# ao.net
KiCad netlist of a schematic drawn in Altium Designer
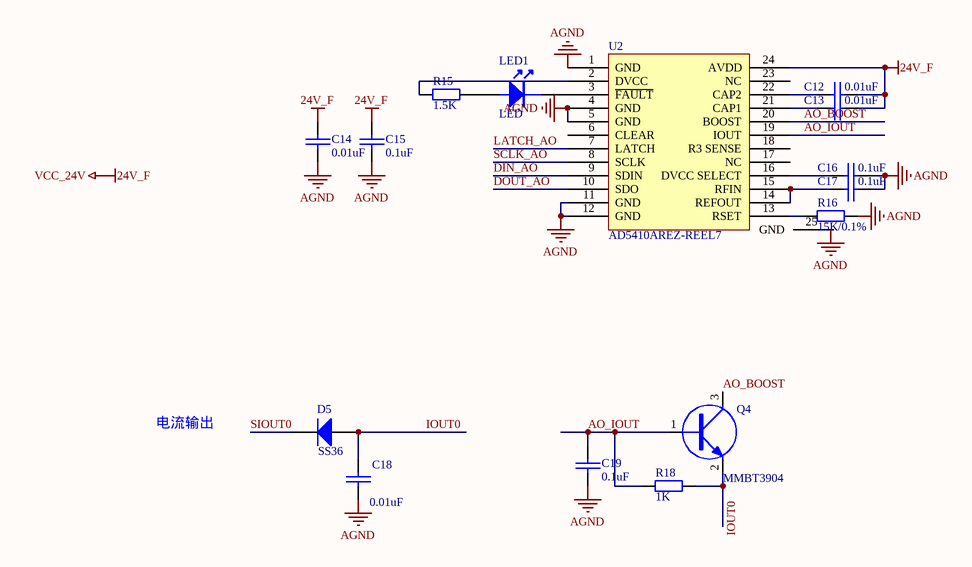
[diagram p0: ao.SchDoc]

(export (version "E")
  (design (tool "Eeschema 10.0.6"))
  (components
    (comp (ref "C12")
      (value "0.01uF")
      (footprint "0603C")
      (description "Capacitor")
      (libsource (lib "*") (part "CAP"))
    )
    (comp (ref "C13")
      (value "0.01uF")
      (footprint "0603C")
      (description "Capacitor")
      (libsource (lib "*") (part "CAP"))
    )
    (comp (ref "C14")
      (value "0.01uF")
      (footprint "0603C")
      (description "Capacitor")
      (libsource (lib "*") (part "CAP"))
    )
    (comp (ref "C15")
      (value "0.1uF")
      (footprint "0603C")
      (description "Capacitor")
      (libsource (lib "*") (part "CAP"))
    )
    (comp (ref "C16")
      (value "0.1uF")
      (footprint "0603C")
      (description "Capacitor")
      (libsource (lib "*") (part "CAP"))
    )
    (comp (ref "C17")
      (value "0.1uF")
      (footprint "0603C")
      (description "Capacitor")
      (libsource (lib "*") (part "CAP"))
    )
    (comp (ref "C18")
      (value "0.01uF")
      (footprint "0603C")
      (description "Capacitor")
      (libsource (lib "*") (part "CAP"))
    )
    (comp (ref "C19")
      (value "0.1uF")
      (footprint "0603C")
      (description "Capacitor")
      (libsource (lib "*") (part "CAP"))
    )
    (comp (ref "D5")
      (value "SS36")
      (footprint "sma")
      (description "1 Amp General Purpose Rectifier")
      (fields (field (name "PUBLISHER") "Altium Limited"))
      (libsource (lib "Miscellaneous Devices") (part "1N4001"))
    )
    (comp (ref "LED1") (value "LED") (footprint "0603LED") (libsource (lib "*") (part "LED")))
    (comp (ref "Q4")
      (value "MMBT3904")
      (footprint "SOT23-3")
      (libsource (lib "CenLib") (part "NPN_MMBT3904"))
    )
    (comp (ref "R15") (value "1.5K") (footprint "0603R") (libsource (lib "MQlibrary") (part "Res0805M")))
    (comp (ref "R16") (value "15K/0.1%") (footprint "0603R") (libsource (lib "MQlibrary") (part "Res0805M")))
    (comp (ref "R18") (value "1K") (footprint "0603R") (libsource (lib "MQlibrary") (part "Res0805M")))
    (comp (ref "U2")
      (value "AD5410AREZ-REEL7")
      (footprint "AD5410AREZ-REEL7")
      (libsource (lib "Schlib1") (part "AD5410AREZ-REEL7"))
    )
  )
  (nets
    (net (code "2") (name "/AO_BOOST") (class "Default")
      (node (ref "Q4") (pin "3") (pinfunction "C_3") (pintype "passive"))
      (node (ref "U2") (pin "20") (pinfunction "BOOST_20") (pintype "passive"))
    )
    (net (code "3") (name "/AO_IOUT") (class "Default")
      (node (ref "C19") (pin "2") (pinfunction "2_2") (pintype "passive"))
      (node (ref "Q4") (pin "1") (pinfunction "B_1") (pintype "passive"))
      (node (ref "R18") (pin "1") (pinfunction "1_1") (pintype "passive"))
      (node (ref "U2") (pin "19") (pinfunction "IOUT_19") (pintype "passive"))
    )
    (net (code "4") (name "/DIN_AO") (class "Default")
      (node (ref "U2") (pin "9") (pinfunction "SDIN_9") (pintype "passive"))
    )
    (net (code "5") (name "/DOUT_AO") (class "Default")
      (node (ref "U2") (pin "10") (pinfunction "SDO_10") (pintype "passive"))
    )
    (net (code "6") (name "/IOUT0") (class "Default")
      (node (ref "C18") (pin "2") (pinfunction "2_2") (pintype "passive"))
      (node (ref "D5") (pin "1") (pinfunction "A_1") (pintype "passive"))
      (node (ref "Q4") (pin "2") (pinfunction "E_2") (pintype "passive"))
      (node (ref "R18") (pin "2") (pinfunction "2_2") (pintype "passive"))
    )
    (net (code "7") (name "/LATCH_AO") (class "Default")
      (node (ref "U2") (pin "7") (pinfunction "LATCH_7") (pintype "passive"))
    )
    (net (code "8") (name "/SCLK_AO") (class "Default")
      (node (ref "U2") (pin "8") (pinfunction "SCLK_8") (pintype "passive"))
    )
    (net (code "9") (name "/SIOUT0") (class "Default")
      (node (ref "D5") (pin "2") (pinfunction "K_2") (pintype "passive"))
    )
    (net (code "10") (name "24V_F") (class "Default")
      (node (ref "C12") (pin "2") (pinfunction "2_2") (pintype "passive"))
      (node (ref "C13") (pin "2") (pinfunction "2_2") (pintype "passive"))
      (node (ref "C14") (pin "2") (pinfunction "2_2") (pintype "passive"))
      (node (ref "C15") (pin "2") (pinfunction "2_2") (pintype "passive"))
      (node (ref "U2") (pin "24") (pinfunction "AVDD_24") (pintype "passive"))
    )
    (net (code "11") (name "AGND") (class "Default")
      (node (ref "C14") (pin "1") (pinfunction "1_1") (pintype "passive"))
      (node (ref "C15") (pin "1") (pinfunction "1_1") (pintype "passive"))
      (node (ref "C16") (pin "2") (pinfunction "2_2") (pintype "passive"))
      (node (ref "C17") (pin "2") (pinfunction "2_2") (pintype "passive"))
      (node (ref "C18") (pin "1") (pinfunction "1_1") (pintype "passive"))
      (node (ref "C19") (pin "1") (pinfunction "1_1") (pintype "passive"))
      (node (ref "R16") (pin "2") (pinfunction "2_2") (pintype "passive"))
      (node (ref "U2") (pin "1") (pinfunction "GND_1") (pintype "passive"))
      (node (ref "U2") (pin "11") (pinfunction "GND_11") (pintype "passive"))
      (node (ref "U2") (pin "12") (pinfunction "GND_12") (pintype "passive"))
      (node (ref "U2") (pin "4") (pinfunction "GND_4") (pintype "passive"))
      (node (ref "U2") (pin "5") (pinfunction "GND_5") (pintype "passive"))
    )
    (net (code "12") (name "Net-(LED1-Pad1)") (class "Default")
      (node (ref "LED1") (pin "1") (pinfunction "1_1") (pintype "passive"))
      (node (ref "R15") (pin "2") (pinfunction "2_2") (pintype "passive"))
    )
    (net (code "13") (name "Net-(U2-CAP1)") (class "Default")
      (node (ref "C13") (pin "1") (pinfunction "1_1") (pintype "passive"))
      (node (ref "U2") (pin "21") (pinfunction "CAP1_21") (pintype "passive"))
    )
    (net (code "14") (name "Net-(U2-CAP2)") (class "Default")
      (node (ref "C12") (pin "1") (pinfunction "1_1") (pintype "passive"))
      (node (ref "U2") (pin "22") (pinfunction "CAP2_22") (pintype "passive"))
    )
    (net (code "15") (name "Net-(U2-DVCC)") (class "Default")
      (node (ref "R15") (pin "1") (pinfunction "1_1") (pintype "passive"))
      (node (ref "U2") (pin "2") (pinfunction "DVCC_2") (pintype "passive"))
    )
    (net (code "16") (name "Net-(U2-DVCC_SELECT)") (class "Default")
      (node (ref "C16") (pin "1") (pinfunction "1_1") (pintype "passive"))
      (node (ref "U2") (pin "16") (pinfunction "DVCC_SELECT_16") (pintype "passive"))
    )
    (net (code "17") (name "Net-(U2-REFOUT)") (class "Default")
      (node (ref "C17") (pin "1") (pinfunction "1_1") (pintype "passive"))
      (node (ref "U2") (pin "14") (pinfunction "REFOUT_14") (pintype "passive"))
      (node (ref "U2") (pin "15") (pinfunction "RFIN_15") (pintype "passive"))
    )
    (net (code "18") (name "Net-(U2-RSET)") (class "Default")
      (node (ref "R16") (pin "1") (pinfunction "1_1") (pintype "passive"))
      (node (ref "U2") (pin "13") (pinfunction "RSET_13") (pintype "passive"))
    )
    (net (code "19") (name "Net-(U2-~{FAULT})") (class "Default")
      (node (ref "LED1") (pin "2") (pinfunction "2_2") (pintype "passive"))
      (node (ref "U2") (pin "3") (pinfunction "~{FAULT}_3") (pintype "passive"))
    )
    (net (code "20") (name "unconnected-(U2-CLEAR-Pad6)") (class "Default")
      (node (ref "U2") (pin "6") (pinfunction "CLEAR_6") (pintype "passive"))
    )
    (net (code "21") (name "unconnected-(U2-GND-Pad25)") (class "Default")
      (node (ref "U2") (pin "25") (pinfunction "GND_25") (pintype "passive"))
    )
    (net (code "22") (name "unconnected-(U2-NC-Pad17)") (class "Default")
      (node (ref "U2") (pin "17") (pinfunction "NC_17") (pintype "passive"))
    )
    (net (code "23") (name "unconnected-(U2-NC-Pad23)") (class "Default")
      (node (ref "U2") (pin "23") (pinfunction "NC_23") (pintype "passive"))
    )
    (net (code "24") (name "unconnected-(U2-R3_SENSE-Pad18)") (class "Default")
      (node (ref "U2") (pin "18") (pinfunction "R3_SENSE_18") (pintype "passive"))
    )
  )
)
